# chicker.net
KiCad netlist of a schematic drawn in Altium Designer
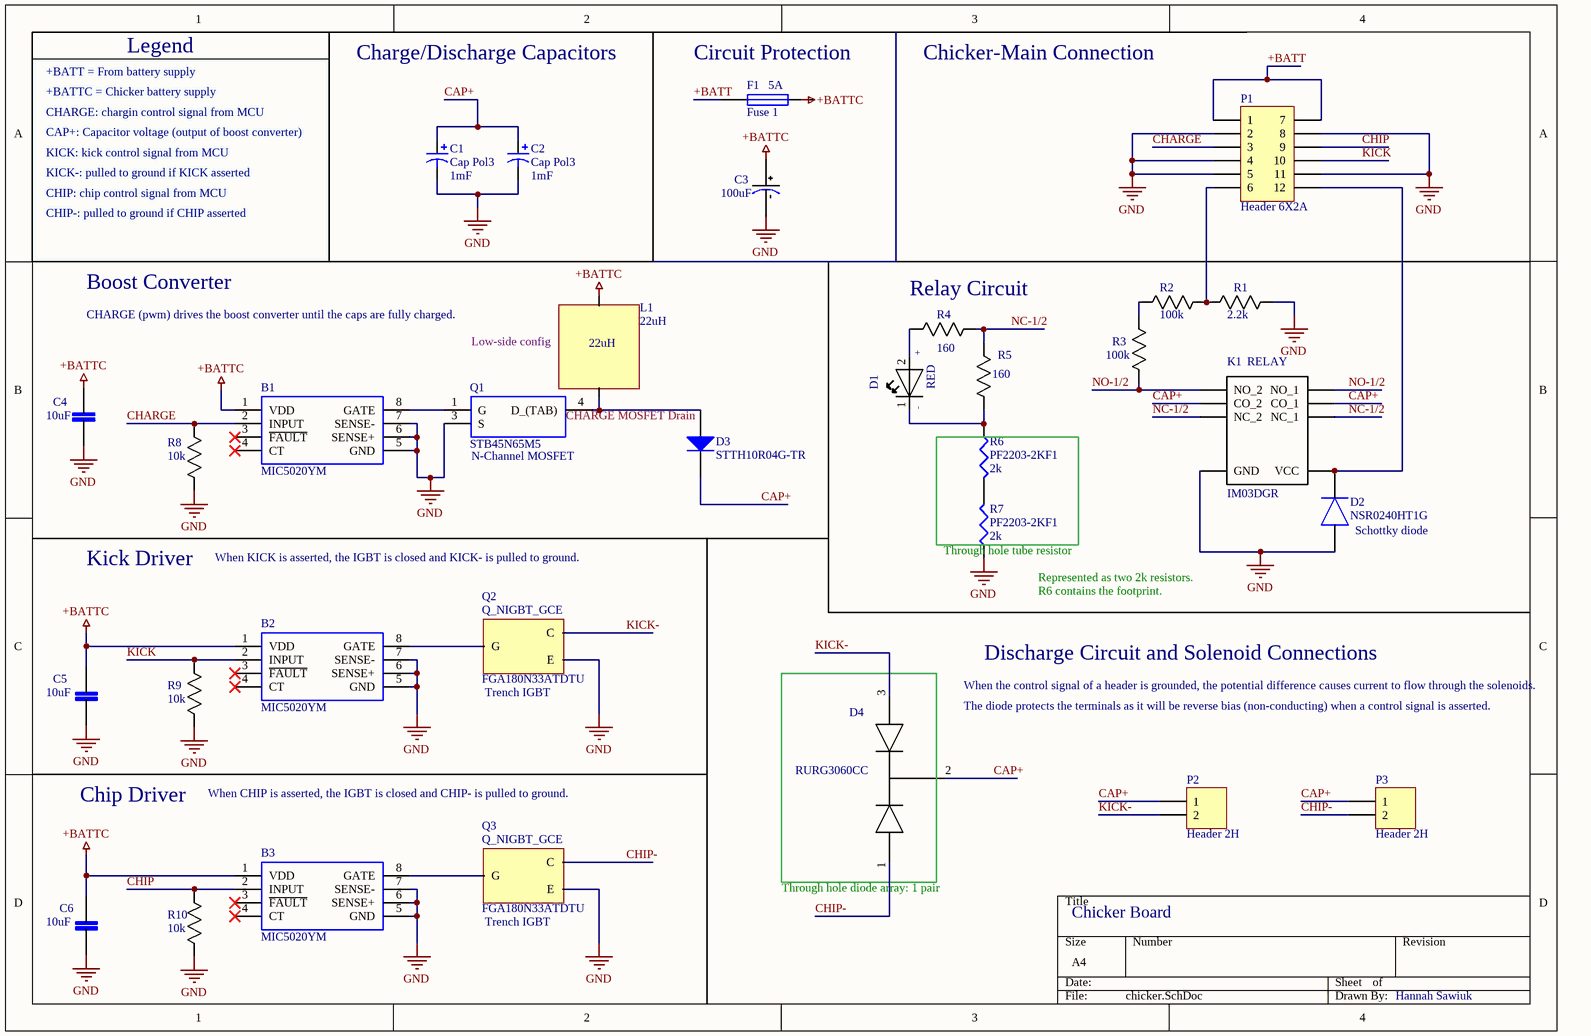
[diagram p0: chicker.SchDoc]

(export (version "E")
  (design (tool "Eeschema 10.0.6"))
  (components
    (comp (ref "B1")
      (value "MIC5020YM")
      (footprint "SOIC127P600X188-8N")
      (description "Low-Side Gate Driver IC Non-Inverting 8-SOIC")
      (fields (field (name "MP") "Microchip") (field (name "DIGI-KEY_PART_NUM") "576-1818-5-ND"))
      (libsource (lib "MIC5020YM") (part "MIC5020YM"))
    )
    (comp (ref "B2")
      (value "MIC5020YM")
      (footprint "SOIC127P600X188-8N")
      (description "Low-Side Gate Driver IC Non-Inverting 8-SOIC")
      (fields (field (name "MP") "Microchip") (field (name "DIGI-KEY_PART_NUM") "576-1818-5-ND"))
      (libsource (lib "MIC5020YM") (part "MIC5020YM"))
    )
    (comp (ref "B3")
      (value "MIC5020YM")
      (footprint "SOIC127P600X188-8N")
      (description "Low-Side Gate Driver IC Non-Inverting 8-SOIC")
      (fields (field (name "MP") "Microchip") (field (name "DIGI-KEY_PART_NUM") "576-1818-5-ND"))
      (libsource (lib "MIC5020YM") (part "MIC5020YM"))
    )
    (comp (ref "C1")
      (value "Cap Pol3")
      (footprint "C0805")
      (description "Polarized Capacitor (Surface Mount)")
      (fields
        (field (name "ALTIUM_VALUE") "1mF")
        (field (name "DIGI-KEY_PART_NUM") "565-2754-ND")
        (field (name "MF") "United Chemi-Con")
      )
      (libsource (lib "Miscellaneous Devices") (part "Cap Pol3"))
    )
    (comp (ref "C2")
      (value "Cap Pol3")
      (footprint "C0805")
      (description "Polarized Capacitor (Surface Mount)")
      (fields
        (field (name "ALTIUM_VALUE") "1mF")
        (field (name "DIGI-KEY_PART_NUM") "565-2754-ND")
        (field (name "MF") "United Chemi-Con")
      )
      (libsource (lib "Miscellaneous Devices") (part "Cap Pol3"))
    )
    (comp (ref "C3")
      (value "100uF")
      (footprint "CAPPRD350W60D800H1150B_ECA-1HM101(Primary)")
      (description "CAP ALUM 100UF 20% 50V RADIAL")
      (fields (field (name "MF") "Panasonic") (field (name "MP") "ECA-1HM101"))
      (libsource (lib "ECA-1HM101") (part "ECA-1HM101"))
    )
    (comp (ref "C4")
      (value "10uF")
      (footprint "CAPC3216X100N")
      (description "CAP CER 10UF 25V X5R 1206")
      (fields (field (name "MF") "Samsung") (field (name "MP") "CL31A106KAHNNNE"))
      (libsource (lib "CL31A226KOCLFNC") (part "CL31A226KOCLFNC"))
    )
    (comp (ref "C5")
      (value "10uF")
      (footprint "CAPC3216X100N")
      (description "CAP CER 10UF 25V X5R 1206")
      (fields (field (name "MF") "Samsung") (field (name "MP") "CL31A106KAHNNNE"))
      (libsource (lib "") (part "CL31A226KOCLFNC_1"))
    )
    (comp (ref "C6")
      (value "10uF")
      (footprint "CAPC3216X100N")
      (description "CAP CER 10UF 25V X5R 1206")
      (fields (field (name "MF") "Samsung") (field (name "MP") "CL31A106KAHNNNE"))
      (libsource (lib "") (part "CL31A226KOCLFNC_1"))
    )
    (comp (ref "D1")
      (value "RED")
      (footprint "WL-SMRW-1206-RECT")
      (description "LED RED CLEAR 1206 SMD")
      (fields (field (name "MF") "Lite-On Inc.") (field (name "MP") "LTST-C150CKT"))
      (libsource (lib "WL-SMRW") (part "WL-SMRW"))
    )
    (comp (ref "D2")
      (value "NSR0240HT1G")
      (footprint "SOD2512X110N")
      (description "SMT Schottky Diode, 40V dc 250mA, 3ns, 2-pin SOD-323")
      (fields (field (name "MF") "ON Semiconductor") (field (name "RS PART NUMBER") "7931024P"))
      (libsource (lib "NSR0240HT1G") (part "NSR0240HT1G"))
    )
    (comp (ref "D3")
      (value "STTH10R04G-TR")
      (footprint "DPAK508P1542X460-3N")
      (description "DIODE GEN PURP 400V 10A D2PAK")
      (fields (field (name "DIGI-KEY_PART_NUM") "497-7575-1-ND") (field (name "MF") "STMicroelectronics"))
      (libsource (lib "Miscellaneous Devices") (part "Diode 1N914"))
    )
    (comp (ref "D4")
      (value "RURG3060CC")
      (footprint "SOT93_TIP147(Primary)")
      (description "DIODE ARRAY GP 600V 30A TO247")
      (fields (field (name "DIGI-KEY_PART_NUM") "RURG3060CC-ND") (field (name "MF") "On Semiconductor"))
      (libsource (lib "Schematic Components") (part "RURG3060CC"))
    )
    (comp (ref "F1")
      (value "Fuse 1")
      (footprint "FUSM3216X140N")
      (description "FUSE BOARD MOUNT 5A 32VDC 1206")
      (fields (field (name "DIGI-KEY_PART_NUM") "F3539CT-ND") (field (name "MF") "Littelfuse Inc."))
      (libsource (lib "Miscellaneous Devices") (part "Fuse 1"))
    )
    (comp (ref "K1")
      (value "IM03DGR")
      (footprint "GULLWINGS")
      (description "Relay, Signal, Dpdt, 250vac, 220vdc, 5a")
      (fields
        (field (name "MF") "TE Connectivity")
        (field (name "ALTIUM_VALUE") "RELAY")
        (field (name "MOUSER_PART_NUM") "655-IM03DGR")
      )
      (libsource (lib "IM03DGR") (part "IM03DGR"))
    )
    (comp (ref "L1")
      (value "22uH")
      (footprint "PCBComponent_1")
      (libsource (lib "Schematic Components") (part "Inductor 22uH"))
    )
    (comp (ref "P1")
      (value "Header 6X2A")
      (footprint "HDR2X6_CEN")
      (description "Header, 6-Pin, Dual row")
      (fields
        (field (name "DIGI-KEY_PART_NUM") "S2011E-06-ND")
        (field (name "MF") "Sullins Connector Solutions")
        (field (name "PUBLISHER") "Altium Limited")
      )
      (libsource (lib "Miscellaneous Connectors") (part "Header 6X2A"))
    )
    (comp (ref "P2")
      (value "Header 2H")
      (footprint "HDR1X2H")
      (description "2 Positions Header Connector 0.100\" (2.54mm) Through Hole, Right Angle Tin")
      (fields (field (name "DIGI-KEY_PART_NUM") "WM4300-ND") (field (name "MF") "Molex, LLC"))
      (libsource (lib "Miscellaneous Connectors") (part "Header 2H"))
    )
    (comp (ref "P3")
      (value "Header 2H")
      (footprint "HDR1X2H")
      (description "2 Positions Header Connector 0.100\" (2.54mm) Through Hole, Right Angle Tin")
      (fields (field (name "DIGI-KEY_PART_NUM") "WM4300-ND") (field (name "MF") "Molex, LLC"))
      (libsource (lib "Miscellaneous Connectors") (part "Header 2H"))
    )
    (comp (ref "Q1")
      (value "STB45N65M5")
      (footprint "TO254P1542X460-3N")
      (description "MOSFET N CH 650V 35A D2PAK")
      (fields (field (name "MF") "STMicroelectronics") (field (name "DIGI-KEY_PART_NUM") "497-12940-1-ND"))
      (libsource (lib "STB45N65M5") (part "STB45N65M5"))
    )
    (comp (ref "Q2")
      (value "FGA180N33ATDTU")
      (footprint "TO-3PN_V_FDA69N25(Primary)")
      (description "IGBT Trench 330V 180A 390W Through Hole TO-3P")
      (fields (field (name "DIGI-KEY_PART_NUM") "FGA180N33ATDTU-ND") (field (name "MF") "ON Semiconductor"))
      (libsource (lib "Schematic Components") (part "FGA180N33ATDTU"))
    )
    (comp (ref "Q3")
      (value "FGA180N33ATDTU")
      (footprint "TO-3PN_V_FDA69N25(Primary)")
      (description "IGBT Trench 330V 180A 390W Through Hole TO-3P")
      (fields (field (name "DIGI-KEY_PART_NUM") "FGA180N33ATDTU-ND") (field (name "MF") "ON Semiconductor"))
      (libsource (lib "Schematic Components") (part "FGA180N33ATDTU"))
    )
    (comp (ref "R1")
      (value "2.2k")
      (footprint "RESC2013X65N")
      (description "RES SMD 2.2K OHM 1% 1/8W 0805")
      (fields (field (name "MP") "RC0805FR-072K2L") (field (name "MF") "Yageo"))
      (libsource (lib "RC0805FR-072K2L") (part "RC0805FR-072K2L"))
    )
    (comp (ref "R2")
      (value "100k")
      (footprint "RESC2013X65N")
      (description "RES SMD 100K OHM 1% 1/8W 0805")
      (fields (field (name "MP") "RC0805FR-07100KL") (field (name "MF") "Yageo"))
      (libsource (lib "RC0805FR-072K2L") (part "RC0805FR-072K2L"))
    )
    (comp (ref "R3")
      (value "100k")
      (footprint "RESC2013X65N")
      (description "RES SMD 100K OHM 1% 1/8W 0805")
      (fields (field (name "MP") "RC0805FR-07100KL") (field (name "MF") "Yageo"))
      (libsource (lib "RC0805FR-072K2L") (part "RC0805FR-072K2L"))
    )
    (comp (ref "R4")
      (value "160")
      (footprint "RESC2013X65N")
      (description "RES SMD 160 OHM 1% 1/8W 0805")
      (fields (field (name "MP") "RC0805FR-07160RL") (field (name "MF") "Yageo"))
      (libsource (lib "RC0805FR-072K2L") (part "RC0805FR-072K2L"))
    )
    (comp (ref "R5")
      (value "160")
      (footprint "RESC2013X65N")
      (description "RES SMD 160 OHM 1% 1/8W 0805")
      (fields (field (name "MP") "RC0805FR-07160RL") (field (name "MF") "Yageo"))
      (libsource (lib "RC0805FR-072K2L") (part "RC0805FR-072K2L"))
    )
    (comp (ref "R6")
      (value "PF2203-2KF1")
      (footprint "POWER_DIODE")
      (description "RES 2K OHM 35W 1% TO220")
      (fields
        (field (name "ALTIUM_VALUE") "2k")
        (field (name "DIGI-KEY_PART_NUM") "696-1170-ND")
        (field (name "MF") "Riedon")
        (field (name "PUBLISHER") "Altium Limited")
      )
      (libsource (lib "Miscellaneous Devices") (part "Res3"))
    )
    (comp (ref "R7")
      (value "PF2203-2KF1")
      (description "RES 2K OHM 35W 1% TO220")
      (fields
        (field (name "ALTIUM_VALUE") "2k")
        (field (name "DIGI-KEY_PART_NUM") "696-1170-ND")
        (field (name "MF") "Riedon")
        (field (name "PUBLISHER") "Altium Limited")
      )
      (libsource (lib "Miscellaneous Devices") (part "Res3"))
    )
    (comp (ref "R8")
      (value "10k")
      (footprint "RESC2013X65N")
      (description "RES SMD 10K OHM 1% 1/8W 0805")
      (fields (field (name "MP") "RC0805FR-0710KL") (field (name "MF") "Yageo"))
      (libsource (lib "RC0805FR-072K2L") (part "RC0805FR-072K2L"))
    )
    (comp (ref "R9")
      (value "10k")
      (footprint "RESC2013X65N")
      (description "RES SMD 10K OHM 1% 1/8W 0805")
      (fields (field (name "MP") "RC0805FR-0710KL") (field (name "MF") "Yageo"))
      (libsource (lib "RC0805FR-072K2L") (part "RC0805FR-072K2L"))
    )
    (comp (ref "R10")
      (value "10k")
      (footprint "RESC2013X65N")
      (description "RES SMD 10K OHM 1% 1/8W 0805")
      (fields (field (name "MP") "RC0805FR-0710KL") (field (name "MF") "Yageo"))
      (libsource (lib "RC0805FR-072K2L") (part "RC0805FR-072K2L"))
    )
  )
  (nets
    (net (code "1") (name "+BATTC") (class "Default")
      (node (ref "B1") (pin "1") (pinfunction "VDD_1") (pintype "power_in"))
      (node (ref "B2") (pin "1") (pinfunction "VDD_1") (pintype "power_in"))
      (node (ref "B3") (pin "1") (pinfunction "VDD_1") (pintype "power_in"))
      (node (ref "C3") (pin "POS") (pinfunction "POS_POS") (pintype "passive"))
      (node (ref "C4") (pin "1") (pinfunction "1_1") (pintype "passive"))
      (node (ref "C5") (pin "1") (pinfunction "1_1") (pintype "passive"))
      (node (ref "C6") (pin "1") (pinfunction "1_1") (pintype "passive"))
      (node (ref "L1") (pin "1") (pinfunction "1_1") (pintype "passive"))
    )
    (net (code "2") (name "/+BATT") (class "Default")
      (node (ref "F1") (pin "2") (pinfunction "2_2") (pintype "passive"))
      (node (ref "P1") (pin "1") (pinfunction "1_1") (pintype "passive"))
      (node (ref "P1") (pin "7") (pinfunction "7_7") (pintype "passive"))
    )
    (net (code "3") (name "/CAP+") (class "Default")
      (node (ref "C1") (pin "1") (pinfunction "1_1") (pintype "passive"))
      (node (ref "C2") (pin "1") (pinfunction "1_1") (pintype "passive"))
      (node (ref "D3") (pin "2") (pinfunction "K_2") (pintype "passive"))
      (node (ref "D4") (pin "2") (pinfunction "6_2") (pintype "passive"))
      (node (ref "K1") (pin "3") (pinfunction "CO_1_3") (pintype "passive"))
      (node (ref "K1") (pin "6") (pinfunction "CO_2_6") (pintype "passive"))
      (node (ref "P2") (pin "1") (pinfunction "1_1") (pintype "passive"))
      (node (ref "P3") (pin "1") (pinfunction "1_1") (pintype "passive"))
    )
    (net (code "4") (name "/CHARGE") (class "Default")
      (node (ref "B1") (pin "2") (pinfunction "INPUT_2") (pintype "passive"))
      (node (ref "P1") (pin "3") (pinfunction "3_3") (pintype "passive"))
      (node (ref "R8") (pin "1") (pinfunction "R1_1") (pintype "passive"))
    )
    (net (code "5") (name "/CHIP") (class "Default")
      (node (ref "B3") (pin "2") (pinfunction "INPUT_2") (pintype "passive"))
      (node (ref "P1") (pin "9") (pinfunction "9_9") (pintype "passive"))
      (node (ref "R10") (pin "1") (pinfunction "R1_1") (pintype "passive"))
    )
    (net (code "6") (name "/CHIP-") (class "Default")
      (node (ref "D4") (pin "1") (pinfunction "7_1") (pintype "passive"))
      (node (ref "P3") (pin "2") (pinfunction "2_2") (pintype "passive"))
      (node (ref "Q3") (pin "4") (pinfunction "C_4") (pintype "passive"))
    )
    (net (code "7") (name "/KICK") (class "Default")
      (node (ref "B2") (pin "2") (pinfunction "INPUT_2") (pintype "passive"))
      (node (ref "P1") (pin "10") (pinfunction "10_10") (pintype "passive"))
      (node (ref "R9") (pin "1") (pinfunction "R1_1") (pintype "passive"))
    )
    (net (code "8") (name "/KICK-") (class "Default")
      (node (ref "D4") (pin "3") (pinfunction "1_3") (pintype "passive"))
      (node (ref "P2") (pin "2") (pinfunction "2_2") (pintype "passive"))
      (node (ref "Q2") (pin "4") (pinfunction "C_4") (pintype "passive"))
    )
    (net (code "9") (name "/NC-1{slash}2") (class "Default")
      (node (ref "K1") (pin "2") (pinfunction "NC_1_2") (pintype "passive"))
      (node (ref "K1") (pin "7") (pinfunction "NC_2_7") (pintype "passive"))
      (node (ref "R4") (pin "1") (pinfunction "R1_1") (pintype "passive"))
      (node (ref "R5") (pin "2") (pinfunction "R2_2") (pintype "passive"))
    )
    (net (code "10") (name "/NO-1{slash}2") (class "Default")
      (node (ref "K1") (pin "4") (pinfunction "NO_1_4") (pintype "passive"))
      (node (ref "K1") (pin "5") (pinfunction "NO_2_5") (pintype "passive"))
      (node (ref "R3") (pin "1") (pinfunction "R1_1") (pintype "passive"))
    )
    (net (code "11") (name "GND") (class "Default")
      (node (ref "B1") (pin "5") (pinfunction "GND_5") (pintype "passive"))
      (node (ref "B1") (pin "6") (pinfunction "SENSE+_6") (pintype "passive"))
      (node (ref "B1") (pin "7") (pinfunction "SENSE-_7") (pintype "passive"))
      (node (ref "B2") (pin "5") (pinfunction "GND_5") (pintype "passive"))
      (node (ref "B2") (pin "6") (pinfunction "SENSE+_6") (pintype "passive"))
      (node (ref "B2") (pin "7") (pinfunction "SENSE-_7") (pintype "passive"))
      (node (ref "B3") (pin "5") (pinfunction "GND_5") (pintype "passive"))
      (node (ref "B3") (pin "6") (pinfunction "SENSE+_6") (pintype "passive"))
      (node (ref "B3") (pin "7") (pinfunction "SENSE-_7") (pintype "passive"))
      (node (ref "C1") (pin "2") (pinfunction "2_2") (pintype "passive"))
      (node (ref "C2") (pin "2") (pinfunction "2_2") (pintype "passive"))
      (node (ref "C3") (pin "NEG") (pinfunction "NEG_NEG") (pintype "passive"))
      (node (ref "C4") (pin "2") (pinfunction "2_2") (pintype "passive"))
      (node (ref "C5") (pin "2") (pinfunction "2_2") (pintype "passive"))
      (node (ref "C6") (pin "2") (pinfunction "2_2") (pintype "passive"))
      (node (ref "D2") (pin "2") (pinfunction "A_2") (pintype "passive"))
      (node (ref "K1") (pin "8") (pinfunction "GND_8") (pintype "power_in"))
      (node (ref "P1") (pin "11") (pinfunction "11_11") (pintype "passive"))
      (node (ref "P1") (pin "2") (pinfunction "2_2") (pintype "passive"))
      (node (ref "P1") (pin "4") (pinfunction "4_4") (pintype "passive"))
      (node (ref "P1") (pin "5") (pinfunction "5_5") (pintype "passive"))
      (node (ref "P1") (pin "8") (pinfunction "8_8") (pintype "passive"))
      (node (ref "Q1") (pin "3") (pinfunction "S_3") (pintype "passive"))
      (node (ref "Q2") (pin "3") (pinfunction "E_3") (pintype "passive"))
      (node (ref "Q3") (pin "3") (pinfunction "E_3") (pintype "passive"))
      (node (ref "R1") (pin "1") (pinfunction "R1_1") (pintype "passive"))
      (node (ref "R10") (pin "2") (pinfunction "R2_2") (pintype "passive"))
      (node (ref "R7") (pin "1") (pinfunction "1_1") (pintype "passive"))
      (node (ref "R8") (pin "2") (pinfunction "R2_2") (pintype "passive"))
      (node (ref "R9") (pin "2") (pinfunction "R2_2") (pintype "passive"))
    )
    (net (code "12") (name "Net-(B1-GATE)") (class "Default")
      (node (ref "B1") (pin "8") (pinfunction "GATE_8") (pintype "passive"))
      (node (ref "Q1") (pin "1") (pinfunction "G_1") (pintype "passive"))
    )
    (net (code "13") (name "Net-(B2-GATE)") (class "Default")
      (node (ref "B2") (pin "8") (pinfunction "GATE_8") (pintype "passive"))
      (node (ref "Q2") (pin "G") (pinfunction "G_G") (pintype "passive"))
    )
    (net (code "14") (name "Net-(B3-GATE)") (class "Default")
      (node (ref "B3") (pin "8") (pinfunction "GATE_8") (pintype "passive"))
      (node (ref "Q3") (pin "G") (pinfunction "G_G") (pintype "passive"))
    )
    (net (code "15") (name "Net-(D1-NEG)") (class "Default")
      (node (ref "D1") (pin "1") (pinfunction "NEG_1") (pintype "bidirectional"))
      (node (ref "R5") (pin "1") (pinfunction "R1_1") (pintype "passive"))
      (node (ref "R6") (pin "1") (pinfunction "1_1") (pintype "passive"))
    )
    (net (code "16") (name "Net-(D1-POS)") (class "Default")
      (node (ref "D1") (pin "2") (pinfunction "POS_2") (pintype "bidirectional"))
      (node (ref "R4") (pin "2") (pinfunction "R2_2") (pintype "passive"))
    )
    (net (code "17") (name "Net-(D2-K)") (class "Default")
      (node (ref "D2") (pin "1") (pinfunction "K_1") (pintype "passive"))
      (node (ref "K1") (pin "1") (pinfunction "VCC_1") (pintype "power_in"))
      (node (ref "P1") (pin "12") (pinfunction "12_12") (pintype "passive"))
    )
    (net (code "18") (name "Net-(D3-A)") (class "Default")
      (node (ref "D3") (pin "1") (pinfunction "A_1") (pintype "passive"))
      (node (ref "L1") (pin "0") (pinfunction "0_0") (pintype "passive"))
      (node (ref "Q1") (pin "4") (pinfunction "D_(TAB)_4") (pintype "passive"))
    )
    (net (code "19") (name "Net-(R1-R2)") (class "Default")
      (node (ref "P1") (pin "6") (pinfunction "6_6") (pintype "passive"))
      (node (ref "R1") (pin "2") (pinfunction "R2_2") (pintype "passive"))
      (node (ref "R2") (pin "2") (pinfunction "R2_2") (pintype "passive"))
    )
    (net (code "20") (name "Net-(R2-R1)") (class "Default")
      (node (ref "R2") (pin "1") (pinfunction "R1_1") (pintype "passive"))
      (node (ref "R3") (pin "2") (pinfunction "R2_2") (pintype "passive"))
    )
    (net (code "21") (name "Net-(R6-Pad2)") (class "Default")
      (node (ref "R6") (pin "2") (pinfunction "2_2") (pintype "passive"))
      (node (ref "R7") (pin "2") (pinfunction "2_2") (pintype "passive"))
    )
    (net (code "22") (name "unconnected-(B1-CT-Pad4)") (class "Default")
      (node (ref "B1") (pin "4") (pinfunction "CT_4") (pintype "passive+no_connect"))
    )
    (net (code "23") (name "unconnected-(B1-FAULT-Pad3)") (class "Default")
      (node (ref "B1") (pin "3") (pinfunction "FAULT_3") (pintype "passive+no_connect"))
    )
    (net (code "24") (name "unconnected-(B2-CT-Pad4)") (class "Default")
      (node (ref "B2") (pin "4") (pinfunction "CT_4") (pintype "passive+no_connect"))
    )
    (net (code "25") (name "unconnected-(B2-FAULT-Pad3)") (class "Default")
      (node (ref "B2") (pin "3") (pinfunction "FAULT_3") (pintype "passive+no_connect"))
    )
    (net (code "26") (name "unconnected-(B3-CT-Pad4)") (class "Default")
      (node (ref "B3") (pin "4") (pinfunction "CT_4") (pintype "passive+no_connect"))
    )
    (net (code "27") (name "unconnected-(B3-FAULT-Pad3)") (class "Default")
      (node (ref "B3") (pin "3") (pinfunction "FAULT_3") (pintype "passive+no_connect"))
    )
    (net (code "28") (name "unconnected-(F1-Pad1)") (class "Default")
      (node (ref "F1") (pin "1") (pinfunction "1_1") (pintype "passive"))
    )
  )
)
